# USB2-HUB.net
KiCad netlist of a schematic drawn in Altium Designer
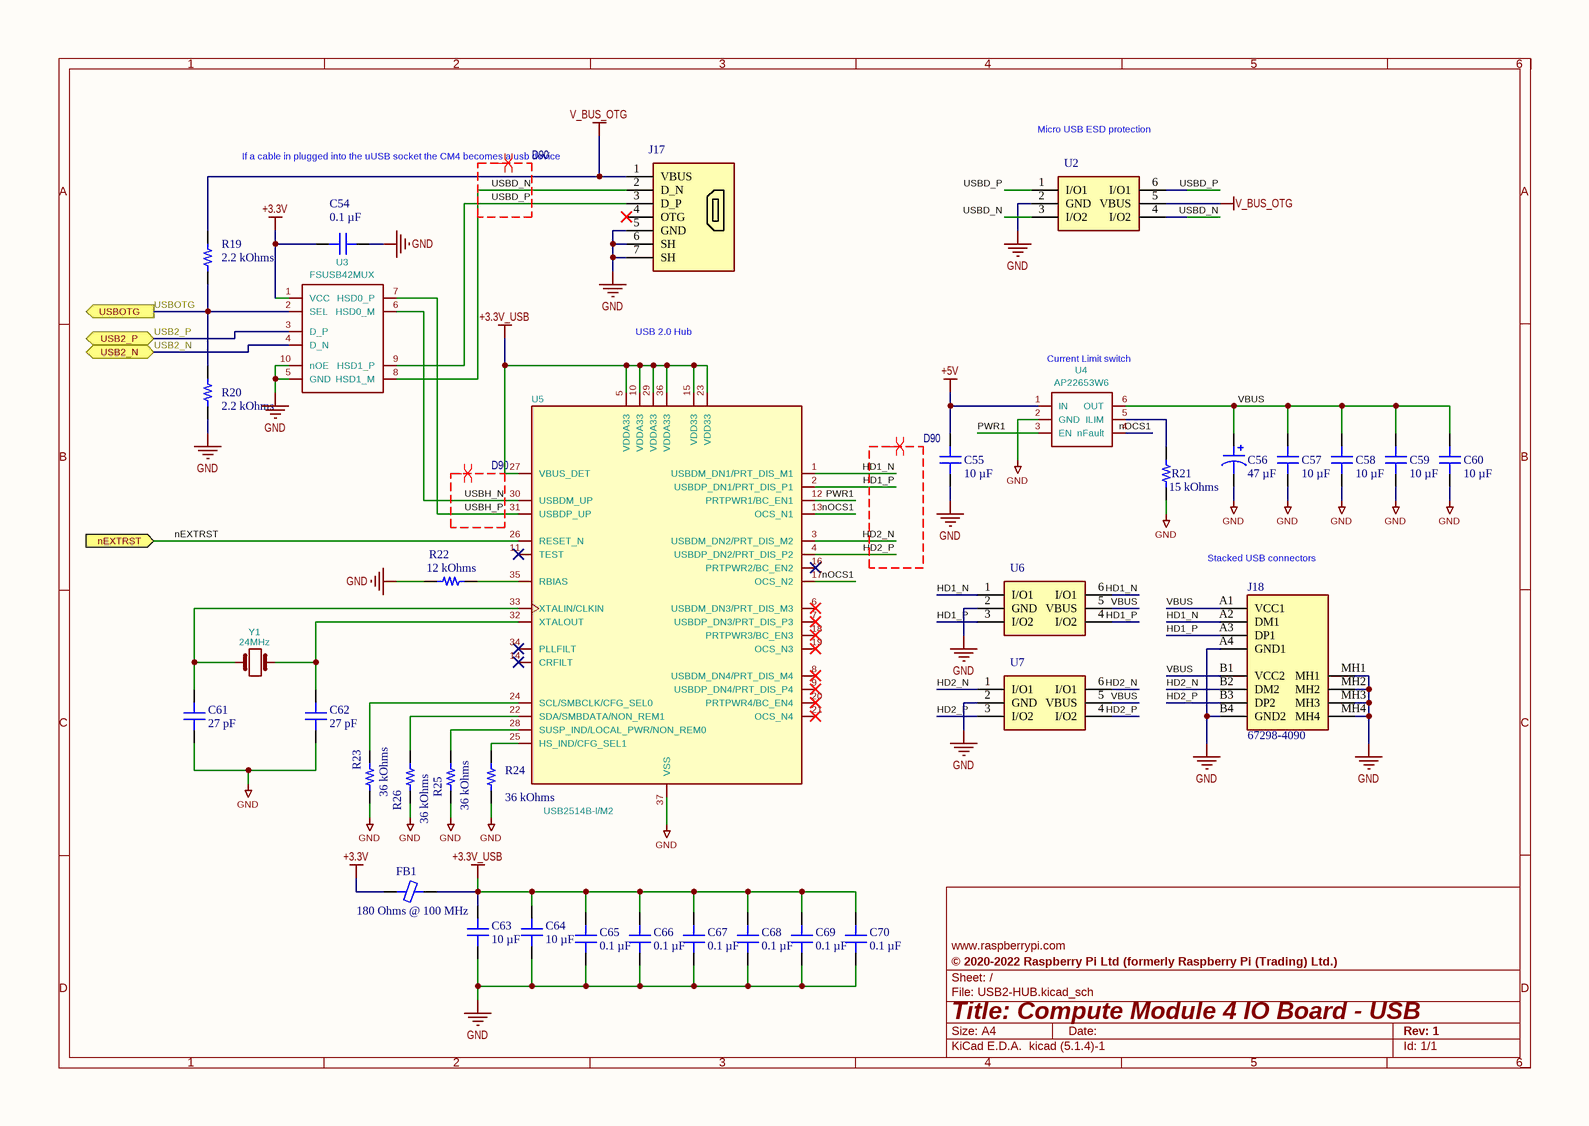
[diagram p0: USB2-HUB.SchDoc]

(export (version "E")
  (design (tool "Eeschema 10.0.6"))
  (components
    (comp (ref "C54")
      (value "0.1 µF")
      (footprint "CAP 0603_1608")
      (description "CAP CER 0.1UF 50V X7R 0603")
      (fields (field (name "PART NUMBER") "CC0603KRX7R9BB104") (field (name "MANUFACTURER") "Yageo"))
      (libsource (lib "Celestial Altium Library - altium_library") (part "Capacitor"))
    )
    (comp (ref "C55")
      (value "10 µF")
      (footprint "CAP 0805_2012")
      (description "CAP CER 10UF 25V X5R 0805")
      (fields (field (name "PART NUMBER") "CC0805KKX5R8BB106") (field (name "MANUFACTURER") "Yageo"))
      (libsource (lib "Celestial Altium Library - altium_library") (part "Capacitor"))
    )
    (comp (ref "C56")
      (value "47 µF")
      (footprint "CAP POL 2917_7343")
      (description "CAP TANT 47UF 10% 35V 2917")
      (fields (field (name "PART NUMBER") "T491X476K035AT") (field (name "MANUFACTURER") "KEMET"))
      (libsource (lib "Celestial Altium Library - altium_library") (part "Polarised Capacitor"))
    )
    (comp (ref "C57")
      (value "10 µF")
      (footprint "CAP 0805_2012")
      (description "CAP CER 10UF 25V X5R 0805")
      (fields (field (name "PART NUMBER") "CC0805KKX5R8BB106") (field (name "MANUFACTURER") "Yageo"))
      (libsource (lib "Celestial Altium Library - altium_library") (part "Capacitor"))
    )
    (comp (ref "C58")
      (value "10 µF")
      (footprint "CAP 0805_2012")
      (description "CAP CER 10UF 25V X5R 0805")
      (fields (field (name "PART NUMBER") "CC0805KKX5R8BB106") (field (name "MANUFACTURER") "Yageo"))
      (libsource (lib "Celestial Altium Library - altium_library") (part "Capacitor"))
    )
    (comp (ref "C59")
      (value "10 µF")
      (footprint "CAP 0805_2012")
      (description "CAP CER 10UF 25V X5R 0805")
      (fields (field (name "PART NUMBER") "CC0805KKX5R8BB106") (field (name "MANUFACTURER") "Yageo"))
      (libsource (lib "Celestial Altium Library - altium_library") (part "Capacitor"))
    )
    (comp (ref "C60")
      (value "10 µF")
      (footprint "CAP 0805_2012")
      (description "CAP CER 10UF 25V X5R 0805")
      (fields (field (name "PART NUMBER") "CC0805KKX5R8BB106") (field (name "MANUFACTURER") "Yageo"))
      (libsource (lib "Celestial Altium Library - altium_library") (part "Capacitor"))
    )
    (comp (ref "C61")
      (value "27 pF")
      (footprint "CAP 0603_1608")
      (description "CAP CER 27PF 100V C0G/NPO 0603")
      (fields (field (name "PART NUMBER") "CC0603GRNPO0BN270") (field (name "MANUFACTURER") "Yageo"))
      (libsource (lib "Celestial Altium Library - altium_library") (part "Capacitor"))
    )
    (comp (ref "C62")
      (value "27 pF")
      (footprint "CAP 0603_1608")
      (description "CAP CER 27PF 100V C0G/NPO 0603")
      (fields (field (name "PART NUMBER") "CC0603GRNPO0BN270") (field (name "MANUFACTURER") "Yageo"))
      (libsource (lib "Celestial Altium Library - altium_library") (part "Capacitor"))
    )
    (comp (ref "C63")
      (value "10 µF")
      (footprint "CAP 0805_2012")
      (description "CAP CER 10UF 25V X5R 0805")
      (fields (field (name "PART NUMBER") "CC0805KKX5R8BB106") (field (name "MANUFACTURER") "Yageo"))
      (libsource (lib "Celestial Altium Library - altium_library") (part "Capacitor"))
    )
    (comp (ref "C64")
      (value "10 µF")
      (footprint "CAP 0805_2012")
      (description "CAP CER 10UF 25V X5R 0805")
      (fields (field (name "PART NUMBER") "CC0805KKX5R8BB106") (field (name "MANUFACTURER") "Yageo"))
      (libsource (lib "Celestial Altium Library - altium_library") (part "Capacitor"))
    )
    (comp (ref "C65")
      (value "0.1 µF")
      (footprint "CAP 0603_1608")
      (description "CAP CER 0.1UF 50V X7R 0603")
      (fields (field (name "PART NUMBER") "CC0603KRX7R9BB104") (field (name "MANUFACTURER") "Yageo"))
      (libsource (lib "Celestial Altium Library - altium_library") (part "Capacitor"))
    )
    (comp (ref "C66")
      (value "0.1 µF")
      (footprint "CAP 0603_1608")
      (description "CAP CER 0.1UF 50V X7R 0603")
      (fields (field (name "PART NUMBER") "CC0603KRX7R9BB104") (field (name "MANUFACTURER") "Yageo"))
      (libsource (lib "Celestial Altium Library - altium_library") (part "Capacitor"))
    )
    (comp (ref "C67")
      (value "0.1 µF")
      (footprint "CAP 0603_1608")
      (description "CAP CER 0.1UF 50V X7R 0603")
      (fields (field (name "PART NUMBER") "CC0603KRX7R9BB104") (field (name "MANUFACTURER") "Yageo"))
      (libsource (lib "Celestial Altium Library - altium_library") (part "Capacitor"))
    )
    (comp (ref "C68")
      (value "0.1 µF")
      (footprint "CAP 0603_1608")
      (description "CAP CER 0.1UF 50V X7R 0603")
      (fields (field (name "PART NUMBER") "CC0603KRX7R9BB104") (field (name "MANUFACTURER") "Yageo"))
      (libsource (lib "Celestial Altium Library - altium_library") (part "Capacitor"))
    )
    (comp (ref "C69")
      (value "0.1 µF")
      (footprint "CAP 0603_1608")
      (description "CAP CER 0.1UF 50V X7R 0603")
      (fields (field (name "PART NUMBER") "CC0603KRX7R9BB104") (field (name "MANUFACTURER") "Yageo"))
      (libsource (lib "Celestial Altium Library - altium_library") (part "Capacitor"))
    )
    (comp (ref "C70")
      (value "0.1 µF")
      (footprint "CAP 0603_1608")
      (description "CAP CER 0.1UF 50V X7R 0603")
      (fields (field (name "PART NUMBER") "CC0603KRX7R9BB104") (field (name "MANUFACTURER") "Yageo"))
      (libsource (lib "Celestial Altium Library - altium_library") (part "Capacitor"))
    )
    (comp (ref "FB1")
      (value "180 Ohms @ 100 MHz")
      (footprint "FER 0603_1608")
      (description "FERRITE BEAD 180 OHM 0603 1LN")
      (fields
        (field (name "PART NUMBER") "BLM18PG181SN1D")
        (field (name "MANUFACTURER") "Murata Electronics")
      )
      (libsource (lib "Celestial Altium Library - altium_library") (part "Ferrite Chip"))
    )
    (comp (ref "J17")
      (value "KLS1-2233B-B")
      (footprint "SamacSys:KLS1-2233B")
      (description "Connector, Micro USB 2.0 Vertical")
      (fields (field (name "MANUFACTURER") "KLS"))
      (libsource (lib "SamacSys") (part "KLS1-2233B-B"))
    )
    (comp (ref "J18")
      (value "67298-4090")
      (footprint "SamacSys:672984090")
      (description "Connector")
      (fields (field (name "MOUSER PART NUMBER") "538-67298-4090"))
      (libsource (lib "SamacSys") (part "67298-4090"))
    )
    (comp (ref "R19")
      (value "2.2 kOhms")
      (footprint "YAGEO RES 0603_1608")
      (description "RES 2.2K OHM 1% 1/10W 0603")
      (fields (field (name "PART NUMBER") "RC0603FR-072K2L") (field (name "MANUFACTURER") "Yageo"))
      (libsource (lib "Celestial Altium Library - altium_library") (part "Resistor"))
    )
    (comp (ref "R20")
      (value "2.2 kOhms")
      (footprint "YAGEO RES 0603_1608")
      (description "RES 2.2K OHM 1% 1/10W 0603")
      (fields (field (name "PART NUMBER") "RC0603FR-072K2L") (field (name "MANUFACTURER") "Yageo"))
      (libsource (lib "Celestial Altium Library - altium_library") (part "Resistor"))
    )
    (comp (ref "R21")
      (value "15 kOhms")
      (footprint "YAGEO RES 0603_1608")
      (description "RES 15K OHM 1% 1/10W 0603")
      (fields (field (name "PART NUMBER") "RC0603FR-0715KL") (field (name "MANUFACTURER") "Yageo"))
      (libsource (lib "Celestial Altium Library - altium_library") (part "Resistor"))
    )
    (comp (ref "R22")
      (value "12 kOhms")
      (footprint "YAGEO RES 0603_1608")
      (description "RES 12K OHM 1% 1/10W 0603")
      (fields (field (name "PART NUMBER") "RC0603FR-0712KL") (field (name "MANUFACTURER") "Yageo"))
      (libsource (lib "Celestial Altium Library - altium_library") (part "Resistor"))
    )
    (comp (ref "R23")
      (value "36 kOhms")
      (footprint "YAGEO RES 0603_1608")
      (description "RES 36K OHM 1% 1/10W 0603")
      (fields (field (name "PART NUMBER") "RC0603FR-0736KL") (field (name "MANUFACTURER") "Yageo"))
      (libsource (lib "Celestial Altium Library - altium_library") (part "Resistor"))
    )
    (comp (ref "R24")
      (value "36 kOhms")
      (footprint "YAGEO RES 0603_1608")
      (description "RES 36K OHM 1% 1/10W 0603")
      (fields (field (name "PART NUMBER") "RC0603FR-0736KL") (field (name "MANUFACTURER") "Yageo"))
      (libsource (lib "Celestial Altium Library - altium_library") (part "Resistor"))
    )
    (comp (ref "R25")
      (value "36 kOhms")
      (footprint "YAGEO RES 0603_1608")
      (description "RES 36K OHM 1% 1/10W 0603")
      (fields (field (name "PART NUMBER") "RC0603FR-0736KL") (field (name "MANUFACTURER") "Yageo"))
      (libsource (lib "Celestial Altium Library - altium_library") (part "Resistor"))
    )
    (comp (ref "R26")
      (value "36 kOhms")
      (footprint "YAGEO RES 0603_1608")
      (description "RES 36K OHM 1% 1/10W 0603")
      (fields (field (name "PART NUMBER") "RC0603FR-0736KL") (field (name "MANUFACTURER") "Yageo"))
      (libsource (lib "Celestial Altium Library - altium_library") (part "Resistor"))
    )
    (comp (ref "U2")
      (value "USBLC6-2SC6")
      (footprint "SamacSys:SOT95P280X145-6N")
      (description "Integrated Circuit")
      (fields (field (name "MOUSER PART NUMBER") "511-USBLC6-2SC6"))
      (libsource (lib "SamacSys") (part "USBLC6-2SC6"))
    )
    (comp (ref "U3")
      (value "FSUSB42MUX")
      (footprint "MSOP-10_3x3mm_P0.5mm")
      (libsource (lib "CM4IO") (part "FSUSB42MX"))
    )
    (comp (ref "U4") (value "AP22653W6") (footprint "SOT-23-6") (libsource (lib "CM4IO") (part "AP2553W6")))
    (comp (ref "U5")
      (value "USB2514B-I/M2")
      (footprint "QFN-36-1EP_6x6mm_P0.5mm_EP3.7x3.7mm")
      (libsource (lib "Interface_USB") (part "USB2514B_Bi"))
    )
    (comp (ref "U6")
      (value "USBLC6-2SC6")
      (footprint "SamacSys:SOT95P280X145-6N")
      (description "Integrated Circuit")
      (fields (field (name "MOUSER PART NUMBER") "511-USBLC6-2SC6"))
      (libsource (lib "SamacSys") (part "USBLC6-2SC6"))
    )
    (comp (ref "U7")
      (value "USBLC6-2SC6")
      (footprint "SamacSys:SOT95P280X145-6N")
      (description "Integrated Circuit")
      (fields (field (name "MOUSER PART NUMBER") "511-USBLC6-2SC6"))
      (libsource (lib "SamacSys") (part "USBLC6-2SC6"))
    )
    (comp (ref "Y1")
      (value "24MHz")
      (footprint "Crystal_SMD_HC49-SD")
      (libsource (lib "Device") (part "Crystal"))
    )
  )
  (nets
    (net (code "1") (name "+3.3V") (class "Default")
      (node (ref "C54") (pin "2") (pinfunction "2_2") (pintype "passive"))
      (node (ref "FB1") (pin "2") (pinfunction "2_2") (pintype "passive"))
      (node (ref "U3") (pin "1") (pinfunction "VCC_1") (pintype "passive"))
    )
    (net (code "2") (name "+3.3V_USB") (class "Default")
      (node (ref "C63") (pin "2") (pinfunction "2_2") (pintype "passive"))
      (node (ref "C64") (pin "2") (pinfunction "2_2") (pintype "passive"))
      (node (ref "C65") (pin "2") (pinfunction "2_2") (pintype "passive"))
      (node (ref "C66") (pin "2") (pinfunction "2_2") (pintype "passive"))
      (node (ref "C67") (pin "2") (pinfunction "2_2") (pintype "passive"))
      (node (ref "C68") (pin "2") (pinfunction "2_2") (pintype "passive"))
      (node (ref "C69") (pin "2") (pinfunction "2_2") (pintype "passive"))
      (node (ref "C70") (pin "2") (pinfunction "2_2") (pintype "passive"))
      (node (ref "FB1") (pin "1") (pinfunction "1_1") (pintype "passive"))
      (node (ref "U5") (pin "10") (pinfunction "VDDA33_10") (pintype "passive"))
      (node (ref "U5") (pin "15") (pinfunction "VDD33_15") (pintype "passive"))
      (node (ref "U5") (pin "23") (pinfunction "VDD33_23") (pintype "passive"))
      (node (ref "U5") (pin "27") (pinfunction "VBUS_DET_27") (pintype "passive"))
      (node (ref "U5") (pin "29") (pinfunction "VDDA33_29") (pintype "passive"))
      (node (ref "U5") (pin "36") (pinfunction "VDDA33_36") (pintype "passive"))
      (node (ref "U5") (pin "5") (pinfunction "VDDA33_5") (pintype "passive"))
    )
    (net (code "3") (name "+5V") (class "Default")
      (node (ref "C55") (pin "2") (pinfunction "2_2") (pintype "passive"))
      (node (ref "U4") (pin "1") (pinfunction "IN_1") (pintype "passive"))
    )
    (net (code "4") (name "/HD1_N") (class "Default")
      (node (ref "J18") (pin "A2") (pinfunction "DM1_A2") (pintype "passive"))
      (node (ref "U5") (pin "1") (pinfunction "USBDM_DN1/PRT_DIS_M1_1") (pintype "passive"))
      (node (ref "U6") (pin "1") (pinfunction "I/O1_1") (pintype "passive"))
      (node (ref "U6") (pin "6") (pinfunction "I/O1_6") (pintype "passive"))
    )
    (net (code "5") (name "/HD1_P") (class "Default")
      (node (ref "J18") (pin "A3") (pinfunction "DP1_A3") (pintype "passive"))
      (node (ref "U5") (pin "2") (pinfunction "USBDP_DN1/PRT_DIS_P1_2") (pintype "passive"))
      (node (ref "U6") (pin "3") (pinfunction "I/O2_3") (pintype "passive"))
      (node (ref "U6") (pin "4") (pinfunction "I/O2_4") (pintype "passive"))
    )
    (net (code "6") (name "/HD2_N") (class "Default")
      (node (ref "J18") (pin "B2") (pinfunction "DM2_B2") (pintype "passive"))
      (node (ref "U5") (pin "3") (pinfunction "USBDM_DN2/PRT_DIS_M2_3") (pintype "passive"))
      (node (ref "U7") (pin "1") (pinfunction "I/O1_1") (pintype "passive"))
      (node (ref "U7") (pin "6") (pinfunction "I/O1_6") (pintype "passive"))
    )
    (net (code "7") (name "/HD2_P") (class "Default")
      (node (ref "J18") (pin "B3") (pinfunction "DP2_B3") (pintype "passive"))
      (node (ref "U5") (pin "4") (pinfunction "USBDP_DN2/PRT_DIS_P2_4") (pintype "passive"))
      (node (ref "U7") (pin "3") (pinfunction "I/O2_3") (pintype "passive"))
      (node (ref "U7") (pin "4") (pinfunction "I/O2_4") (pintype "passive"))
    )
    (net (code "8") (name "/PWR1") (class "Default")
      (node (ref "U4") (pin "3") (pinfunction "EN_3") (pintype "passive"))
      (node (ref "U5") (pin "12") (pinfunction "PRTPWR1/BC_EN1_12") (pintype "passive"))
    )
    (net (code "9") (name "/USB2_N") (class "Default")
      (node (ref "U3") (pin "4") (pinfunction "D_N_4") (pintype "passive"))
    )
    (net (code "10") (name "/USB2_P") (class "Default")
      (node (ref "U3") (pin "3") (pinfunction "D_P_3") (pintype "passive"))
    )
    (net (code "11") (name "/USBD_N") (class "Default")
      (node (ref "J17") (pin "2") (pinfunction "D_N_2") (pintype "passive"))
      (node (ref "U2") (pin "3") (pinfunction "I/O2_3") (pintype "passive"))
      (node (ref "U2") (pin "4") (pinfunction "I/O2_4") (pintype "passive"))
      (node (ref "U3") (pin "8") (pinfunction "HSD1_M_8") (pintype "passive"))
    )
    (net (code "12") (name "/USBD_P") (class "Default")
      (node (ref "J17") (pin "3") (pinfunction "D_P_3") (pintype "passive"))
      (node (ref "U2") (pin "1") (pinfunction "I/O1_1") (pintype "passive"))
      (node (ref "U2") (pin "6") (pinfunction "I/O1_6") (pintype "passive"))
      (node (ref "U3") (pin "9") (pinfunction "HSD1_P_9") (pintype "passive"))
    )
    (net (code "13") (name "/USBH_N") (class "Default")
      (node (ref "U3") (pin "6") (pinfunction "HSD0_M_6") (pintype "passive"))
      (node (ref "U5") (pin "30") (pinfunction "USBDM_UP_30") (pintype "passive"))
    )
    (net (code "14") (name "/USBH_P") (class "Default")
      (node (ref "U3") (pin "7") (pinfunction "HSD0_P_7") (pintype "passive"))
      (node (ref "U5") (pin "31") (pinfunction "USBDP_UP_31") (pintype "passive"))
    )
    (net (code "15") (name "/USBOTG") (class "Default")
      (node (ref "R19") (pin "1") (pinfunction "1_1") (pintype "passive"))
      (node (ref "R20") (pin "2") (pinfunction "2_2") (pintype "passive"))
      (node (ref "U3") (pin "2") (pinfunction "SEL_2") (pintype "passive"))
    )
    (net (code "16") (name "/VBUS") (class "Default")
      (node (ref "C56") (pin "1") (pinfunction "1_1") (pintype "passive"))
      (node (ref "C57") (pin "2") (pinfunction "2_2") (pintype "passive"))
      (node (ref "C58") (pin "2") (pinfunction "2_2") (pintype "passive"))
      (node (ref "C59") (pin "2") (pinfunction "2_2") (pintype "passive"))
      (node (ref "C60") (pin "2") (pinfunction "2_2") (pintype "passive"))
      (node (ref "J18") (pin "A1") (pinfunction "VCC1_A1") (pintype "passive"))
      (node (ref "J18") (pin "B1") (pinfunction "VCC2_B1") (pintype "passive"))
      (node (ref "U4") (pin "6") (pinfunction "OUT_6") (pintype "passive"))
      (node (ref "U6") (pin "5") (pinfunction "VBUS_5") (pintype "passive"))
      (node (ref "U7") (pin "5") (pinfunction "VBUS_5") (pintype "passive"))
    )
    (net (code "17") (name "/nEXTRST") (class "Default")
      (node (ref "U5") (pin "26") (pinfunction "RESET_N_26") (pintype "passive"))
    )
    (net (code "18") (name "/nOCS1") (class "Default")
      (node (ref "U4") (pin "4") (pinfunction "nFault_4") (pintype "passive"))
      (node (ref "U5") (pin "13") (pinfunction "OCS_N1_13") (pintype "passive"))
      (node (ref "U5") (pin "17") (pinfunction "OCS_N2_17") (pintype "passive"))
    )
    (net (code "19") (name "GND") (class "Default")
      (node (ref "C54") (pin "1") (pinfunction "1_1") (pintype "passive"))
      (node (ref "C55") (pin "1") (pinfunction "1_1") (pintype "passive"))
      (node (ref "C56") (pin "2") (pinfunction "2_2") (pintype "passive"))
      (node (ref "C57") (pin "1") (pinfunction "1_1") (pintype "passive"))
      (node (ref "C58") (pin "1") (pinfunction "1_1") (pintype "passive"))
      (node (ref "C59") (pin "1") (pinfunction "1_1") (pintype "passive"))
      (node (ref "C60") (pin "1") (pinfunction "1_1") (pintype "passive"))
      (node (ref "C61") (pin "1") (pinfunction "1_1") (pintype "passive"))
      (node (ref "C62") (pin "1") (pinfunction "1_1") (pintype "passive"))
      (node (ref "C63") (pin "1") (pinfunction "1_1") (pintype "passive"))
      (node (ref "C64") (pin "1") (pinfunction "1_1") (pintype "passive"))
      (node (ref "C65") (pin "1") (pinfunction "1_1") (pintype "passive"))
      (node (ref "C66") (pin "1") (pinfunction "1_1") (pintype "passive"))
      (node (ref "C67") (pin "1") (pinfunction "1_1") (pintype "passive"))
      (node (ref "C68") (pin "1") (pinfunction "1_1") (pintype "passive"))
      (node (ref "C69") (pin "1") (pinfunction "1_1") (pintype "passive"))
      (node (ref "C70") (pin "1") (pinfunction "1_1") (pintype "passive"))
      (node (ref "J17") (pin "5") (pinfunction "GND_5") (pintype "passive"))
      (node (ref "J17") (pin "6") (pinfunction "SH_6") (pintype "passive"))
      (node (ref "J17") (pin "7") (pinfunction "SH_7") (pintype "passive"))
      (node (ref "J18") (pin "A4") (pinfunction "GND1_A4") (pintype "passive"))
      (node (ref "J18") (pin "B4") (pinfunction "GND2_B4") (pintype "passive"))
      (node (ref "J18") (pin "MH1") (pinfunction "MH1_MH1") (pintype "passive"))
      (node (ref "J18") (pin "MH2") (pinfunction "MH2_MH2") (pintype "passive"))
      (node (ref "J18") (pin "MH3") (pinfunction "MH3_MH3") (pintype "passive"))
      (node (ref "J18") (pin "MH4") (pinfunction "MH4_MH4") (pintype "passive"))
      (node (ref "R20") (pin "1") (pinfunction "1_1") (pintype "passive"))
      (node (ref "R21") (pin "1") (pinfunction "1_1") (pintype "passive"))
      (node (ref "R22") (pin "2") (pinfunction "2_2") (pintype "passive"))
      (node (ref "R23") (pin "2") (pinfunction "2_2") (pintype "passive"))
      (node (ref "R24") (pin "2") (pinfunction "2_2") (pintype "passive"))
      (node (ref "R25") (pin "2") (pinfunction "2_2") (pintype "passive"))
      (node (ref "R26") (pin "2") (pinfunction "2_2") (pintype "passive"))
      (node (ref "U2") (pin "2") (pinfunction "GND_2") (pintype "passive"))
      (node (ref "U3") (pin "10") (pinfunction "nOE_10") (pintype "passive"))
      (node (ref "U3") (pin "5") (pinfunction "GND_5") (pintype "passive"))
      (node (ref "U4") (pin "2") (pinfunction "GND_2") (pintype "passive"))
      (node (ref "U5") (pin "37") (pinfunction "VSS_37") (pintype "passive"))
      (node (ref "U6") (pin "2") (pinfunction "GND_2") (pintype "passive"))
      (node (ref "U7") (pin "2") (pinfunction "GND_2") (pintype "passive"))
    )
    (net (code "20") (name "Net-(U4-ILIM)") (class "Default")
      (node (ref "R21") (pin "2") (pinfunction "2_2") (pintype "passive"))
      (node (ref "U4") (pin "5") (pinfunction "ILIM_5") (pintype "passive"))
    )
    (net (code "21") (name "Net-(U5-HS_IND{slash}CFG_SEL1)") (class "Default")
      (node (ref "R24") (pin "1") (pinfunction "1_1") (pintype "passive"))
      (node (ref "U5") (pin "25") (pinfunction "HS_IND/CFG_SEL1_25") (pintype "passive"))
    )
    (net (code "22") (name "Net-(U5-RBIAS)") (class "Default")
      (node (ref "R22") (pin "1") (pinfunction "1_1") (pintype "passive"))
      (node (ref "U5") (pin "35") (pinfunction "RBIAS_35") (pintype "passive"))
    )
    (net (code "23") (name "Net-(U5-SCL{slash}SMBCLK{slash}CFG_SEL0)") (class "Default")
      (node (ref "R23") (pin "1") (pinfunction "1_1") (pintype "passive"))
      (node (ref "U5") (pin "24") (pinfunction "SCL/SMBCLK/CFG_SEL0_24") (pintype "passive"))
    )
    (net (code "24") (name "Net-(U5-SDA{slash}SMBDATA{slash}NON_REM1)") (class "Default")
      (node (ref "R26") (pin "1") (pinfunction "1_1") (pintype "passive"))
      (node (ref "U5") (pin "22") (pinfunction "SDA/SMBDATA/NON_REM1_22") (pintype "passive"))
    )
    (net (code "25") (name "Net-(U5-SUSP_IND{slash}LOCAL_PWR{slash}NON_REM0)") (class "Default")
      (node (ref "R25") (pin "1") (pinfunction "1_1") (pintype "passive"))
      (node (ref "U5") (pin "28") (pinfunction "SUSP_IND/LOCAL_PWR/NON_REM0_28") (pintype "passive"))
    )
    (net (code "26") (name "Net-(U5-XTALIN{slash}CLKIN)") (class "Default")
      (node (ref "C61") (pin "2") (pinfunction "2_2") (pintype "passive"))
      (node (ref "U5") (pin "33") (pinfunction "XTALIN/CLKIN_33") (pintype "passive"))
      (node (ref "Y1") (pin "1") (pinfunction "1_1") (pintype "passive"))
    )
    (net (code "27") (name "Net-(U5-XTALOUT)") (class "Default")
      (node (ref "C62") (pin "2") (pinfunction "2_2") (pintype "passive"))
      (node (ref "U5") (pin "32") (pinfunction "XTALOUT_32") (pintype "passive"))
      (node (ref "Y1") (pin "2") (pinfunction "2_2") (pintype "passive"))
    )
    (net (code "28") (name "V_BUS_OTG") (class "Default")
      (node (ref "J17") (pin "1") (pinfunction "VBUS_1") (pintype "passive"))
      (node (ref "R19") (pin "2") (pinfunction "2_2") (pintype "passive"))
      (node (ref "U2") (pin "5") (pinfunction "VBUS_5") (pintype "passive"))
    )
    (net (code "29") (name "unconnected-(J17-OTG-Pad4)") (class "Default")
      (node (ref "J17") (pin "4") (pinfunction "OTG_4") (pintype "passive+no_connect"))
    )
    (net (code "30") (name "unconnected-(U5-CRFILT-Pad14)") (class "Default")
      (node (ref "U5") (pin "14") (pinfunction "CRFILT_14") (pintype "passive+no_connect"))
    )
    (net (code "31") (name "unconnected-(U5-OCS_N3-Pad19)") (class "Default")
      (node (ref "U5") (pin "19") (pinfunction "OCS_N3_19") (pintype "passive+no_connect"))
    )
    (net (code "32") (name "unconnected-(U5-OCS_N4-Pad21)") (class "Default")
      (node (ref "U5") (pin "21") (pinfunction "OCS_N4_21") (pintype "passive+no_connect"))
    )
    (net (code "33") (name "unconnected-(U5-PLLFILT-Pad34)") (class "Default")
      (node (ref "U5") (pin "34") (pinfunction "PLLFILT_34") (pintype "passive+no_connect"))
    )
    (net (code "34") (name "unconnected-(U5-PRTPWR2{slash}BC_EN2-Pad16)") (class "Default")
      (node (ref "U5") (pin "16") (pinfunction "PRTPWR2/BC_EN2_16") (pintype "passive+no_connect"))
    )
    (net (code "35") (name "unconnected-(U5-PRTPWR3{slash}BC_EN3-Pad18)") (class "Default")
      (node (ref "U5") (pin "18") (pinfunction "PRTPWR3/BC_EN3_18") (pintype "passive+no_connect"))
    )
    (net (code "36") (name "unconnected-(U5-PRTPWR4{slash}BC_EN4-Pad20)") (class "Default")
      (node (ref "U5") (pin "20") (pinfunction "PRTPWR4/BC_EN4_20") (pintype "passive+no_connect"))
    )
    (net (code "37") (name "unconnected-(U5-TEST-Pad11)") (class "Default")
      (node (ref "U5") (pin "11") (pinfunction "TEST_11") (pintype "passive+no_connect"))
    )
    (net (code "38") (name "unconnected-(U5-USBDM_DN3{slash}PRT_DIS_M3-Pad6)") (class "Default")
      (node (ref "U5") (pin "6") (pinfunction "USBDM_DN3/PRT_DIS_M3_6") (pintype "passive+no_connect"))
    )
    (net (code "39") (name "unconnected-(U5-USBDM_DN4{slash}PRT_DIS_M4-Pad8)") (class "Default")
      (node (ref "U5") (pin "8") (pinfunction "USBDM_DN4/PRT_DIS_M4_8") (pintype "passive+no_connect"))
    )
    (net (code "40") (name "unconnected-(U5-USBDP_DN3{slash}PRT_DIS_P3-Pad7)") (class "Default")
      (node (ref "U5") (pin "7") (pinfunction "USBDP_DN3/PRT_DIS_P3_7") (pintype "passive+no_connect"))
    )
    (net (code "41") (name "unconnected-(U5-USBDP_DN4{slash}PRT_DIS_P4-Pad9)") (class "Default")
      (node (ref "U5") (pin "9") (pinfunction "USBDP_DN4/PRT_DIS_P4_9") (pintype "passive+no_connect"))
    )
  )
)
